# CW-Oscillator.net
KiCad netlist of a schematic drawn in Altium Designer
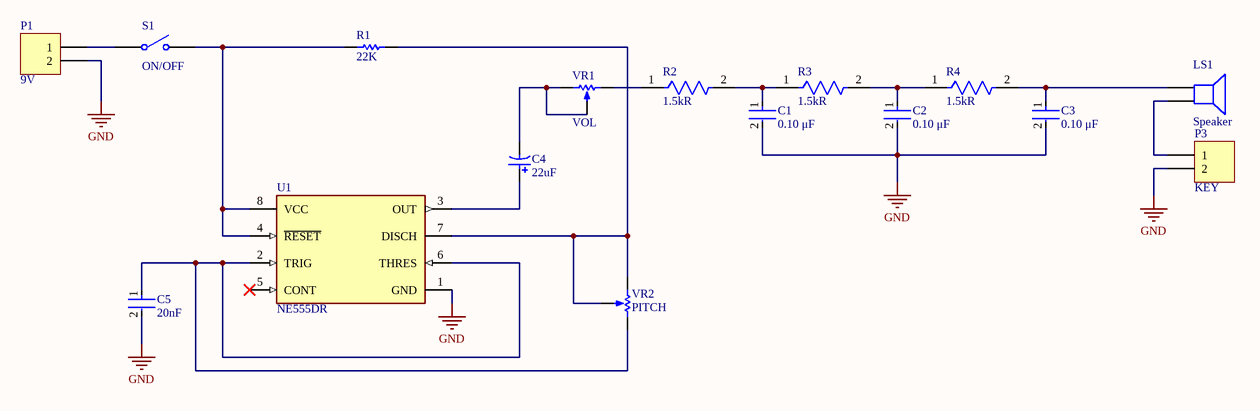
[diagram p0: CW-Oscillator.SchDoc]

(export (version "E")
  (design (tool "Eeschema 10.0.6"))
  (components
    (comp (ref "C1")
      (value "0.10 μF")
      (footprint "FP-C0805C-DN-MFG")
      (description "CAP CER 0.1UF 50V X7R 0805")
      (fields
        (field (name "MANUFACTURER PART NUMBER") "C0805C104K5RACTU")
        (field (name "MANUFACTURER") "KEMET")
      )
      (libsource (lib "Altium Content Vault") (part "b4654b650e69147ec39a6b967a45e02"))
    )
    (comp (ref "C2")
      (value "0.10 μF")
      (footprint "FP-C0805C-DN-MFG")
      (description "CAP CER 0.1UF 50V X7R 0805")
      (fields
        (field (name "MANUFACTURER PART NUMBER") "C0805C104K5RACTU")
        (field (name "MANUFACTURER") "KEMET")
      )
      (libsource (lib "Altium Content Vault") (part "b4654b650e69147ec39a6b967a45e02"))
    )
    (comp (ref "C3")
      (value "0.10 μF")
      (footprint "FP-C0805C-DN-MFG")
      (description "CAP CER 0.1UF 50V X7R 0805")
      (fields
        (field (name "MANUFACTURER PART NUMBER") "C0805C104K5RACTU")
        (field (name "MANUFACTURER") "KEMET")
      )
      (libsource (lib "Altium Content Vault") (part "b4654b650e69147ec39a6b967a45e02"))
    )
    (comp (ref "C4")
      (value "22uF")
      (footprint "CAPPR55-200-1100X500X1200")
      (description "Aluminum Electrolytic Capacitor, 22 uF, +/- 20%, 50 V, -40 to 85 degC, 2-Pin THD, RoHS, Bulk")
      (fields (field (name "VOLTAGE") "50V") (field (name "MANUFACTURER") "Panasonic"))
      (libsource (lib "Altium Content Vault") (part "CAP-P-2"))
    )
    (comp (ref "C5")
      (value "20nF")
      (footprint "FP-GRM21B-0_1-IPC_B")
      (description "Chip Multilayer Ceramic Capacitors for General Purpose, 0805, 20000pF, C0G, 30ppm/°C, 5%, 50V")
      (fields (field (name "TOLERANCE") "5%"))
      (libsource (lib "Altium Content Vault") (part "b4654b650e69147ec39a6b967a45e02"))
    )
    (comp (ref "LS1")
      (value "Speaker")
      (footprint "PIN2")
      (description "Loudspeaker")
      (fields (field (name "PUBLISHER") "Altium Limited"))
      (libsource (lib "Miscellaneous Devices") (part "Speaker"))
    )
    (comp (ref "P1")
      (value "9V")
      (footprint "HDR1X2")
      (description "Header, 2-Pin")
      (fields (field (name "PUBLISHER") "Altium Limited"))
      (libsource (lib "Miscellaneous Connectors") (part "Header 2"))
    )
    (comp (ref "P3")
      (value "KEY")
      (footprint "HDR1X2")
      (description "Header, 2-Pin")
      (fields (field (name "PUBLISHER") "Altium Limited"))
      (libsource (lib "") (part "Header 2_1"))
    )
    (comp (ref "R1")
      (value "22K")
      (footprint "RESA60-630X240")
      (description "Axial Resistor, 22.1 KOhm, +/- 1%, 0.25 W, -55 to 155 degC, 2-Pin THD, RoHS, Bulk")
      (fields (field (name "TOLERANCE") "20%"))
      (libsource (lib "Altium Content Vault") (part "RES-2"))
    )
    (comp (ref "R2")
      (value "1.5kR")
      (footprint "FP-ERJ6EN-MFG")
      (description "RES SMD 1.5K OHM 1% 1/8W 0805")
      (fields (field (name "TOLERANCE") "1%"))
      (libsource (lib "Altium Content Vault") (part "1029c3af85768c4190bb7ad29bc67b5"))
    )
    (comp (ref "R3")
      (value "1.5kR")
      (footprint "FP-ERJ6EN-MFG")
      (description "RES SMD 1.5K OHM 1% 1/8W 0805")
      (fields (field (name "TOLERANCE") "1%"))
      (libsource (lib "Altium Content Vault") (part "1029c3af85768c4190bb7ad29bc67b5"))
    )
    (comp (ref "R4")
      (value "1.5kR")
      (footprint "FP-ERJ6EN-MFG")
      (description "RES SMD 1.5K OHM 1% 1/8W 0805")
      (fields (field (name "TOLERANCE") "1%"))
      (libsource (lib "Altium Content Vault") (part "1029c3af85768c4190bb7ad29bc67b5"))
    )
    (comp (ref "S1")
      (value "ON/OFF")
      (footprint "SPST-2")
      (description "Single-Pole, Single-Throw Switch")
      (fields (field (name "PUBLISHER") "Altium Limited"))
      (libsource (lib "Miscellaneous Devices") (part "SW-SPST"))
    )
    (comp (ref "U1")
      (value "NE555DR")
      (footprint "FP-D0008A-IPC_A")
      (description "IC OSC SGL TIMER 100KHZ 8-SOIC")
      (libsource (lib "Altium Content Vault") (part "a29bba90211dec1890110b94dad7d53"))
    )
    (comp (ref "VR1")
      (value "VOL")
      (footprint "BOUR-3362P")
      (description "Square Trimpot(R) Trimming Potentiometer, 10 KOhm, 300 V, -55 to 125 degC, 3-Pin THD, RoHS, Tube")
      (fields (field (name "TOLERANCE") "1%"))
      (libsource (lib "Altium Content Vault") (part "RES-POT-3"))
    )
    (comp (ref "VR2")
      (value "PITCH")
      (footprint "BOUR-3362P")
      (description "Square Trimpot(R) Trimming Potentiometer, 100 KOhm, 300 V, -55 to 125 degC, 3-Pin THD, RoHS, Tube")
      (fields (field (name "TOLERANCE") "1%"))
      (libsource (lib "Altium Content Vault") (part "RES-POT-3"))
    )
  )
  (nets
    (net (code "1") (name "GND") (class "Default")
      (node (ref "C1") (pin "2") (pinfunction "2_2") (pintype "passive"))
      (node (ref "C2") (pin "2") (pinfunction "2_2") (pintype "passive"))
      (node (ref "C3") (pin "2") (pinfunction "2_2") (pintype "passive"))
      (node (ref "C5") (pin "2") (pinfunction "2_2") (pintype "passive"))
      (node (ref "P1") (pin "2") (pinfunction "2_2") (pintype "passive"))
      (node (ref "P3") (pin "2") (pinfunction "2_2") (pintype "passive"))
      (node (ref "U1") (pin "1") (pinfunction "GND_1") (pintype "power_in"))
    )
    (net (code "2") (name "Net-(C1-Pad1)") (class "Default")
      (node (ref "C1") (pin "1") (pinfunction "1_1") (pintype "passive"))
      (node (ref "R2") (pin "2") (pinfunction "2_2") (pintype "passive"))
      (node (ref "R3") (pin "1") (pinfunction "1_1") (pintype "passive"))
    )
    (net (code "3") (name "Net-(C2-Pad1)") (class "Default")
      (node (ref "C2") (pin "1") (pinfunction "1_1") (pintype "passive"))
      (node (ref "R3") (pin "2") (pinfunction "2_2") (pintype "passive"))
      (node (ref "R4") (pin "1") (pinfunction "1_1") (pintype "passive"))
    )
    (net (code "4") (name "Net-(C3-Pad1)") (class "Default")
      (node (ref "C3") (pin "1") (pinfunction "1_1") (pintype "passive"))
      (node (ref "LS1") (pin "1") (pinfunction "1_1") (pintype "passive"))
      (node (ref "R4") (pin "2") (pinfunction "2_2") (pintype "passive"))
    )
    (net (code "5") (name "Net-(LS1-Pad2)") (class "Default")
      (node (ref "LS1") (pin "2") (pinfunction "2_2") (pintype "passive"))
      (node (ref "P3") (pin "1") (pinfunction "1_1") (pintype "passive"))
    )
    (net (code "6") (name "Net-(S1-COMMON)") (class "Default")
      (node (ref "P1") (pin "1") (pinfunction "1_1") (pintype "passive"))
      (node (ref "S1") (pin "1") (pinfunction "COMMON_1") (pintype "passive"))
    )
    (net (code "7") (name "Net-(S1-NO)") (class "Default")
      (node (ref "R1") (pin "2") (pinfunction "2_2") (pintype "passive"))
      (node (ref "S1") (pin "2") (pinfunction "NO_2") (pintype "passive"))
      (node (ref "U1") (pin "4") (pinfunction "~{RESET}_4") (pintype "input"))
      (node (ref "U1") (pin "8") (pinfunction "VCC_8") (pintype "power_in"))
    )
    (net (code "8") (name "Net-(U1-DISCH)") (class "Default")
      (node (ref "R1") (pin "1") (pinfunction "1_1") (pintype "passive"))
      (node (ref "U1") (pin "7") (pinfunction "DISCH_7") (pintype "open_collector"))
      (node (ref "VR2") (pin "1") (pinfunction "CCW_1") (pintype "passive"))
      (node (ref "VR2") (pin "2") (pinfunction "S_2") (pintype "passive"))
    )
    (net (code "9") (name "Net-(U1-OUT)") (class "Default")
      (node (ref "C4") (pin "1") (pinfunction "1_1") (pintype "passive"))
      (node (ref "U1") (pin "3") (pinfunction "OUT_3") (pintype "output"))
    )
    (net (code "10") (name "Net-(U1-THRES)") (class "Default")
      (node (ref "C5") (pin "1") (pinfunction "1_1") (pintype "passive"))
      (node (ref "U1") (pin "2") (pinfunction "TRIG_2") (pintype "input"))
      (node (ref "U1") (pin "6") (pinfunction "THRES_6") (pintype "input"))
      (node (ref "VR2") (pin "3") (pinfunction "CW_3") (pintype "passive"))
    )
    (net (code "11") (name "Net-(VR1-CCW)") (class "Default")
      (node (ref "C4") (pin "2") (pinfunction "2_2") (pintype "passive"))
      (node (ref "VR1") (pin "1") (pinfunction "CCW_1") (pintype "passive"))
      (node (ref "VR1") (pin "2") (pinfunction "S_2") (pintype "passive"))
    )
    (net (code "12") (name "Net-(VR1-CW)") (class "Default")
      (node (ref "R2") (pin "1") (pinfunction "1_1") (pintype "passive"))
      (node (ref "VR1") (pin "3") (pinfunction "CW_3") (pintype "passive"))
    )
    (net (code "13") (name "unconnected-(U1-CONT-Pad5)") (class "Default")
      (node (ref "U1") (pin "5") (pinfunction "CONT_5") (pintype "input+no_connect"))
    )
  )
)
